# adc.net
KiCad netlist of a schematic drawn in Altium Designer
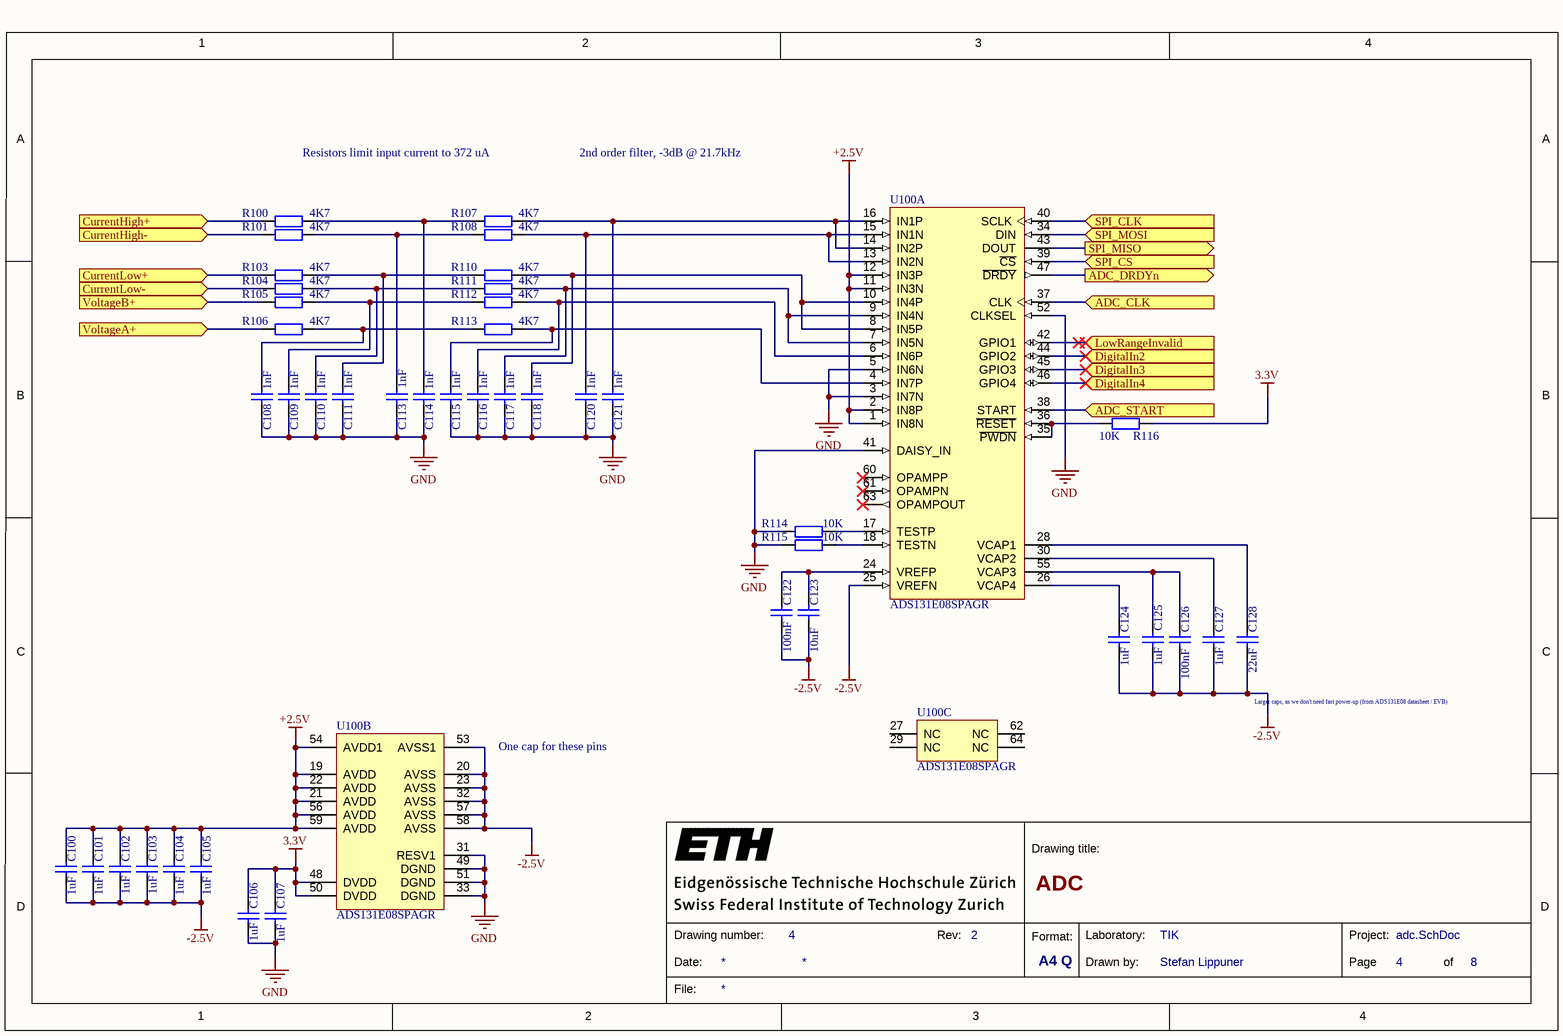
[diagram p0: adc.SchDoc]

(export (version "E")
  (design (tool "Eeschema 10.0.6"))
  (components
    (comp (ref "C100")
      (value "1uF")
      (footprint "CAPC0402(1005)60_L")
      (description "CAP 1uF 16V ±20% 0402 (1005 Metric) Thickness 0.6mm SMD")
      (fields (field (name "TOLERANCE") "Â±20%"))
      (libsource (lib "Altium Content Vault") (part "CMP-1034-02120"))
    )
    (comp (ref "C101")
      (value "1uF")
      (footprint "CAPC0402(1005)60_L")
      (description "CAP 1uF 16V ±20% 0402 (1005 Metric) Thickness 0.6mm SMD")
      (fields (field (name "TOLERANCE") "Â±20%"))
      (libsource (lib "Altium Content Vault") (part "CMP-1034-02120"))
    )
    (comp (ref "C102")
      (value "1uF")
      (footprint "CAPC0402(1005)60_L")
      (description "CAP 1uF 16V ±20% 0402 (1005 Metric) Thickness 0.6mm SMD")
      (fields (field (name "TOLERANCE") "Â±20%"))
      (libsource (lib "Altium Content Vault") (part "CMP-1034-02120"))
    )
    (comp (ref "C103")
      (value "1uF")
      (footprint "CAPC0402(1005)60_L")
      (description "CAP 1uF 16V ±20% 0402 (1005 Metric) Thickness 0.6mm SMD")
      (fields (field (name "TOLERANCE") "Â±20%"))
      (libsource (lib "Altium Content Vault") (part "CMP-1034-02120"))
    )
    (comp (ref "C104")
      (value "1uF")
      (footprint "CAPC0402(1005)60_L")
      (description "CAP 1uF 16V ±20% 0402 (1005 Metric) Thickness 0.6mm SMD")
      (fields (field (name "TOLERANCE") "Â±20%"))
      (libsource (lib "Altium Content Vault") (part "CMP-1034-02120"))
    )
    (comp (ref "C105")
      (value "1uF")
      (footprint "CAPC0402(1005)60_L")
      (description "CAP 1uF 16V ±20% 0402 (1005 Metric) Thickness 0.6mm SMD")
      (fields (field (name "TOLERANCE") "Â±20%"))
      (libsource (lib "Altium Content Vault") (part "CMP-1034-02120"))
    )
    (comp (ref "C106")
      (value "1uF")
      (footprint "CAPC0402(1005)60_L")
      (description "CAP 1uF 16V ±20% 0402 (1005 Metric) Thickness 0.6mm SMD")
      (fields (field (name "TOLERANCE") "Â±20%"))
      (libsource (lib "Altium Content Vault") (part "CMP-1034-02120"))
    )
    (comp (ref "C107")
      (value "1uF")
      (footprint "CAPC0402(1005)60_L")
      (description "CAP 1uF 16V ±20% 0402 (1005 Metric) Thickness 0.6mm SMD")
      (fields (field (name "TOLERANCE") "Â±20%"))
      (libsource (lib "Altium Content Vault") (part "CMP-1034-02120"))
    )
    (comp (ref "C108")
      (value "1nF")
      (footprint "CAPC0402(1005)60_L")
      (description "CAP 1nF 50V ±5% 0402 (1005 Metric) Thickness 0.6mm SMD")
      (fields (field (name "TOLERANCE") "Â±5%"))
      (libsource (lib "Altium Content Vault") (part "CAP"))
    )
    (comp (ref "C109")
      (value "1nF")
      (footprint "CAPC0402(1005)60_L")
      (description "CAP 1nF 50V ±5% 0402 (1005 Metric) Thickness 0.6mm SMD")
      (fields (field (name "TOLERANCE") "Â±5%"))
      (libsource (lib "Altium Content Vault") (part "CAP"))
    )
    (comp (ref "C110")
      (value "1nF")
      (footprint "CAPC0402(1005)60_L")
      (description "CAP 1nF 50V ±5% 0402 (1005 Metric) Thickness 0.6mm SMD")
      (fields (field (name "TOLERANCE") "Â±5%"))
      (libsource (lib "Altium Content Vault") (part "CAP"))
    )
    (comp (ref "C111")
      (value "1nF")
      (footprint "CAPC0402(1005)60_L")
      (description "CAP 1nF 50V ±5% 0402 (1005 Metric) Thickness 0.6mm SMD")
      (fields (field (name "TOLERANCE") "Â±5%"))
      (libsource (lib "Altium Content Vault") (part "CAP"))
    )
    (comp (ref "C113")
      (value "1nF")
      (footprint "CAPC0402(1005)60_L")
      (description "CAP 1nF 50V ±5% 0402 (1005 Metric) Thickness 0.6mm SMD")
      (fields (field (name "TOLERANCE") "Â±5%"))
      (libsource (lib "Altium Content Vault") (part "CAP"))
    )
    (comp (ref "C114")
      (value "1nF")
      (footprint "CAPC0402(1005)60_L")
      (description "CAP 1nF 50V ±5% 0402 (1005 Metric) Thickness 0.6mm SMD")
      (fields (field (name "TOLERANCE") "Â±5%"))
      (libsource (lib "Altium Content Vault") (part "CAP"))
    )
    (comp (ref "C115")
      (value "1nF")
      (footprint "CAPC0402(1005)60_L")
      (description "CAP 1nF 50V ±5% 0402 (1005 Metric) Thickness 0.6mm SMD")
      (fields (field (name "TOLERANCE") "Â±5%"))
      (libsource (lib "Altium Content Vault") (part "CAP"))
    )
    (comp (ref "C116")
      (value "1nF")
      (footprint "CAPC0402(1005)60_L")
      (description "CAP 1nF 50V ±5% 0402 (1005 Metric) Thickness 0.6mm SMD")
      (fields (field (name "TOLERANCE") "Â±5%"))
      (libsource (lib "Altium Content Vault") (part "CAP"))
    )
    (comp (ref "C117")
      (value "1nF")
      (footprint "CAPC0402(1005)60_L")
      (description "CAP 1nF 50V ±5% 0402 (1005 Metric) Thickness 0.6mm SMD")
      (fields (field (name "TOLERANCE") "Â±5%"))
      (libsource (lib "Altium Content Vault") (part "CAP"))
    )
    (comp (ref "C118")
      (value "1nF")
      (footprint "CAPC0402(1005)60_L")
      (description "CAP 1nF 50V ±5% 0402 (1005 Metric) Thickness 0.6mm SMD")
      (fields (field (name "TOLERANCE") "Â±5%"))
      (libsource (lib "Altium Content Vault") (part "CAP"))
    )
    (comp (ref "C120")
      (value "1nF")
      (footprint "CAPC0402(1005)60_L")
      (description "CAP 1nF 50V ±5% 0402 (1005 Metric) Thickness 0.6mm SMD")
      (fields (field (name "TOLERANCE") "Â±5%"))
      (libsource (lib "Altium Content Vault") (part "CAP"))
    )
    (comp (ref "C121")
      (value "1nF")
      (footprint "CAPC0402(1005)60_L")
      (description "CAP 1nF 50V ±5% 0402 (1005 Metric) Thickness 0.6mm SMD")
      (fields (field (name "TOLERANCE") "Â±5%"))
      (libsource (lib "Altium Content Vault") (part "CAP"))
    )
    (comp (ref "C122")
      (value "100nF")
      (footprint "CAPC0402(1005)60_L")
      (description "CAP 100nF 16V -20% to +80% 0402 (1005 Metric) Thickness 0.6mm SMD")
      (fields (field (name "TOLERANCE") "-20% to +80%"))
      (libsource (lib "Altium Content Vault") (part "CMP-1034-02071-1"))
    )
    (comp (ref "C123")
      (value "10uF")
      (footprint "CAPC0603(1608)100_L")
      (description "CAP 10uF 10V ±20% 0603 (1608 Metric) Thickness 1mm SMD")
      (fields (field (name "TOLERANCE") "Â±20%"))
      (libsource (lib "Altium Content Vault") (part "CMP-1035-02800-1"))
    )
    (comp (ref "C124")
      (value "1uF")
      (footprint "CAPC0402(1005)60_L")
      (description "CAP 1uF 16V ±20% 0402 (1005 Metric) Thickness 0.6mm SMD")
      (fields (field (name "TOLERANCE") "Â±20%"))
      (libsource (lib "Altium Content Vault") (part "CMP-1034-02120"))
    )
    (comp (ref "C125")
      (value "1uF")
      (footprint "CAPC0402(1005)60_L")
      (description "CAP 1uF 16V ±20% 0402 (1005 Metric) Thickness 0.6mm SMD")
      (fields (field (name "TOLERANCE") "Â±20%"))
      (libsource (lib "Altium Content Vault") (part "CMP-1034-02120"))
    )
    (comp (ref "C126")
      (value "100nF")
      (footprint "CAPC0402(1005)60_L")
      (description "CAP 100nF 16V -20% to +80% 0402 (1005 Metric) Thickness 0.6mm SMD")
      (fields (field (name "TOLERANCE") "-20% to +80%"))
      (libsource (lib "Altium Content Vault") (part "CMP-1034-02071-1"))
    )
    (comp (ref "C127")
      (value "1uF")
      (footprint "CAPC0402(1005)60_L")
      (description "CAP 1uF 16V ±20% 0402 (1005 Metric) Thickness 0.6mm SMD")
      (fields (field (name "TOLERANCE") "Â±20%"))
      (libsource (lib "Altium Content Vault") (part "CMP-1034-02120"))
    )
    (comp (ref "C128")
      (value "22uF")
      (footprint "CAPC0805(2012)145_L")
      (description "CAP 22uF 6.3V ±10% 0805 (2012 Metric) Thickness 1.45mm SMD")
      (fields (field (name "TOLERANCE") "Â±10%"))
      (libsource (lib "Altium Content Vault") (part "CAP"))
    )
    (comp (ref "R100")
      (value "4K7")
      (footprint "RESC0402(1005)_L")
      (description "4K7 0.063W 1% 0402 (1005 Metric)  SMD")
      (fields (field (name "POWER") "0.063 W") (field (name "TOLERANCE") "1 %"))
      (libsource (lib "Altium Content Vault") (part "RES"))
    )
    (comp (ref "R101")
      (value "4K7")
      (footprint "RESC0402(1005)_L")
      (description "4K7 0.063W 1% 0402 (1005 Metric)  SMD")
      (fields (field (name "POWER") "0.063 W") (field (name "TOLERANCE") "1 %"))
      (libsource (lib "Altium Content Vault") (part "RES"))
    )
    (comp (ref "R103")
      (value "4K7")
      (footprint "RESC0402(1005)_L")
      (description "4K7 0.063W 1% 0402 (1005 Metric)  SMD")
      (fields (field (name "POWER") "0.063 W") (field (name "TOLERANCE") "1 %"))
      (libsource (lib "Altium Content Vault") (part "RES"))
    )
    (comp (ref "R104")
      (value "4K7")
      (footprint "RESC0402(1005)_L")
      (description "4K7 0.063W 1% 0402 (1005 Metric)  SMD")
      (fields (field (name "POWER") "0.063 W") (field (name "TOLERANCE") "1 %"))
      (libsource (lib "Altium Content Vault") (part "RES"))
    )
    (comp (ref "R105")
      (value "4K7")
      (footprint "RESC0402(1005)_L")
      (description "4K7 0.063W 1% 0402 (1005 Metric)  SMD")
      (fields (field (name "POWER") "0.063 W") (field (name "TOLERANCE") "1 %"))
      (libsource (lib "Altium Content Vault") (part "RES"))
    )
    (comp (ref "R106")
      (value "4K7")
      (footprint "RESC0402(1005)_L")
      (description "4K7 0.063W 1% 0402 (1005 Metric)  SMD")
      (fields (field (name "POWER") "0.063 W") (field (name "TOLERANCE") "1 %"))
      (libsource (lib "Altium Content Vault") (part "RES"))
    )
    (comp (ref "R107")
      (value "4K7")
      (footprint "RESC0402(1005)_L")
      (description "4K7 0.063W 1% 0402 (1005 Metric)  SMD")
      (fields (field (name "POWER") "0.063 W") (field (name "TOLERANCE") "1 %"))
      (libsource (lib "Altium Content Vault") (part "RES"))
    )
    (comp (ref "R108")
      (value "4K7")
      (footprint "RESC0402(1005)_L")
      (description "4K7 0.063W 1% 0402 (1005 Metric)  SMD")
      (fields (field (name "POWER") "0.063 W") (field (name "TOLERANCE") "1 %"))
      (libsource (lib "Altium Content Vault") (part "RES"))
    )
    (comp (ref "R110")
      (value "4K7")
      (footprint "RESC0402(1005)_L")
      (description "4K7 0.063W 1% 0402 (1005 Metric)  SMD")
      (fields (field (name "POWER") "0.063 W") (field (name "TOLERANCE") "1 %"))
      (libsource (lib "Altium Content Vault") (part "RES"))
    )
    (comp (ref "R111")
      (value "4K7")
      (footprint "RESC0402(1005)_L")
      (description "4K7 0.063W 1% 0402 (1005 Metric)  SMD")
      (fields (field (name "POWER") "0.063 W") (field (name "TOLERANCE") "1 %"))
      (libsource (lib "Altium Content Vault") (part "RES"))
    )
    (comp (ref "R112")
      (value "4K7")
      (footprint "RESC0402(1005)_L")
      (description "4K7 0.063W 1% 0402 (1005 Metric)  SMD")
      (fields (field (name "POWER") "0.063 W") (field (name "TOLERANCE") "1 %"))
      (libsource (lib "Altium Content Vault") (part "RES"))
    )
    (comp (ref "R113")
      (value "4K7")
      (footprint "RESC0402(1005)_L")
      (description "4K7 0.063W 1% 0402 (1005 Metric)  SMD")
      (fields (field (name "POWER") "0.063 W") (field (name "TOLERANCE") "1 %"))
      (libsource (lib "Altium Content Vault") (part "RES"))
    )
    (comp (ref "R114")
      (value "10K")
      (footprint "RESC0402(1005)_L")
      (description "10K 0.063W 1% 0402 (1005 Metric)  SMD")
      (fields (field (name "TOLERANCE") "1 %") (field (name "POWER") "0.063 W"))
      (libsource (lib "Altium Content Vault") (part "CMP-1011-00623-1"))
    )
    (comp (ref "R115")
      (value "10K")
      (footprint "RESC0402(1005)_L")
      (description "10K 0.063W 1% 0402 (1005 Metric)  SMD")
      (fields (field (name "TOLERANCE") "1 %") (field (name "POWER") "0.063 W"))
      (libsource (lib "Altium Content Vault") (part "CMP-1011-00623-1"))
    )
    (comp (ref "R116")
      (value "10K")
      (footprint "RESC0402(1005)_L")
      (description "10K 0.063W 1% 0402 (1005 Metric)  SMD")
      (fields (field (name "TOLERANCE") "1 %") (field (name "POWER") "0.063 W"))
      (libsource (lib "Altium Content Vault") (part "RES"))
    )
    (comp (ref "U100")
      (value "ADS131E08SPAGR")
      (footprint "QFP50P1000X1000X120_HS-64L")
      (description "Analog to Digital Converters - ADC 8-Channel, 24-Bit, AFE")
      (fields (field (name "MANUFACTURER") "Texas Instruments"))
      (libsource (lib "ETHZ Vault") (part "ADS131E08S"))
    )
  )
  (nets
    (net (code "1") (name "+2.5V") (class "Default")
      (node (ref "C100") (pin "2") (pinfunction "2_2") (pintype "passive"))
      (node (ref "C101") (pin "2") (pinfunction "2_2") (pintype "passive"))
      (node (ref "C102") (pin "2") (pinfunction "2_2") (pintype "passive"))
      (node (ref "C103") (pin "2") (pinfunction "2_2") (pintype "passive"))
      (node (ref "C104") (pin "2") (pinfunction "2_2") (pintype "passive"))
      (node (ref "C105") (pin "2") (pinfunction "2_2") (pintype "passive"))
      (node (ref "U100") (pin "1") (pinfunction "IN8N_1") (pintype "input"))
      (node (ref "U100") (pin "11") (pinfunction "IN3N_11") (pintype "input"))
      (node (ref "U100") (pin "12") (pinfunction "IN3P_12") (pintype "input"))
      (node (ref "U100") (pin "19") (pinfunction "AVDD_19") (pintype "power_in"))
      (node (ref "U100") (pin "2") (pinfunction "IN8P_2") (pintype "input"))
      (node (ref "U100") (pin "21") (pinfunction "AVDD_21") (pintype "power_in"))
      (node (ref "U100") (pin "22") (pinfunction "AVDD_22") (pintype "power_in"))
      (node (ref "U100") (pin "54") (pinfunction "AVDD1_54") (pintype "power_in"))
      (node (ref "U100") (pin "56") (pinfunction "AVDD_56") (pintype "power_in"))
      (node (ref "U100") (pin "59") (pinfunction "AVDD_59") (pintype "power_in"))
    )
    (net (code "2") (name "-2.5V") (class "Default")
      (node (ref "C100") (pin "1") (pinfunction "1_1") (pintype "passive"))
      (node (ref "C101") (pin "1") (pinfunction "1_1") (pintype "passive"))
      (node (ref "C102") (pin "1") (pinfunction "1_1") (pintype "passive"))
      (node (ref "C103") (pin "1") (pinfunction "1_1") (pintype "passive"))
      (node (ref "C104") (pin "1") (pinfunction "1_1") (pintype "passive"))
      (node (ref "C105") (pin "1") (pinfunction "1_1") (pintype "passive"))
      (node (ref "C122") (pin "1") (pinfunction "1_1") (pintype "passive"))
      (node (ref "C123") (pin "1") (pinfunction "1_1") (pintype "passive"))
      (node (ref "C124") (pin "1") (pinfunction "1_1") (pintype "passive"))
      (node (ref "C125") (pin "1") (pinfunction "1_1") (pintype "passive"))
      (node (ref "C126") (pin "1") (pinfunction "1_1") (pintype "passive"))
      (node (ref "C127") (pin "1") (pinfunction "1_1") (pintype "passive"))
      (node (ref "C128") (pin "1") (pinfunction "1_1") (pintype "passive"))
      (node (ref "U100") (pin "20") (pinfunction "AVSS_20") (pintype "power_in"))
      (node (ref "U100") (pin "23") (pinfunction "AVSS_23") (pintype "power_in"))
      (node (ref "U100") (pin "25") (pinfunction "VREFN_25") (pintype "input"))
      (node (ref "U100") (pin "32") (pinfunction "AVSS_32") (pintype "power_in"))
      (node (ref "U100") (pin "53") (pinfunction "AVSS1_53") (pintype "power_in"))
      (node (ref "U100") (pin "57") (pinfunction "AVSS_57") (pintype "power_in"))
      (node (ref "U100") (pin "58") (pinfunction "AVSS_58") (pintype "power_in"))
    )
    (net (code "3") (name "/ADC_CLK") (class "Default")
      (node (ref "U100") (pin "37") (pinfunction "CLK_37") (pintype "input"))
    )
    (net (code "4") (name "/ADC_DRDYn") (class "Default")
      (node (ref "U100") (pin "47") (pinfunction "~{DRDY}_47") (pintype "output"))
    )
    (net (code "5") (name "/ADC_START") (class "Default")
      (node (ref "U100") (pin "38") (pinfunction "START_38") (pintype "input"))
    )
    (net (code "6") (name "/CurrentHigh+") (class "Default")
      (node (ref "R100") (pin "2") (pinfunction "2_2") (pintype "passive"))
    )
    (net (code "7") (name "/CurrentHigh-") (class "Default")
      (node (ref "R101") (pin "2") (pinfunction "2_2") (pintype "passive"))
    )
    (net (code "8") (name "/CurrentLow+") (class "Default")
      (node (ref "R103") (pin "2") (pinfunction "2_2") (pintype "passive"))
    )
    (net (code "9") (name "/CurrentLow-") (class "Default")
      (node (ref "R104") (pin "2") (pinfunction "2_2") (pintype "passive"))
    )
    (net (code "10") (name "/DigitalIn2") (class "Default")
      (node (ref "U100") (pin "44") (pinfunction "GPIO2_44") (pintype "bidirectional+no_connect"))
    )
    (net (code "11") (name "/DigitalIn3") (class "Default")
      (node (ref "U100") (pin "45") (pinfunction "GPIO3_45") (pintype "bidirectional+no_connect"))
    )
    (net (code "12") (name "/DigitalIn4") (class "Default")
      (node (ref "U100") (pin "46") (pinfunction "GPIO4_46") (pintype "bidirectional+no_connect"))
    )
    (net (code "13") (name "/LowRangeInvalid") (class "Default")
      (node (ref "U100") (pin "42") (pinfunction "GPIO1_42") (pintype "bidirectional+no_connect"))
    )
    (net (code "14") (name "/SPI_CLK") (class "Default")
      (node (ref "U100") (pin "40") (pinfunction "SCLK_40") (pintype "input"))
    )
    (net (code "15") (name "/SPI_CS") (class "Default")
      (node (ref "U100") (pin "39") (pinfunction "~{CS}_39") (pintype "input"))
    )
    (net (code "16") (name "/SPI_MISO") (class "Default")
      (node (ref "U100") (pin "43") (pinfunction "DOUT_43") (pintype "tri_state"))
    )
    (net (code "17") (name "/SPI_MOSI") (class "Default")
      (node (ref "U100") (pin "34") (pinfunction "DIN_34") (pintype "input"))
    )
    (net (code "18") (name "/VoltageA+") (class "Default")
      (node (ref "R106") (pin "2") (pinfunction "2_2") (pintype "passive"))
    )
    (net (code "19") (name "/VoltageB+") (class "Default")
      (node (ref "R105") (pin "2") (pinfunction "2_2") (pintype "passive"))
    )
    (net (code "20") (name "3.3V") (class "Default")
      (node (ref "C106") (pin "2") (pinfunction "2_2") (pintype "passive"))
      (node (ref "C107") (pin "2") (pinfunction "2_2") (pintype "passive"))
      (node (ref "R116") (pin "1") (pinfunction "1_1") (pintype "passive"))
      (node (ref "U100") (pin "48") (pinfunction "DVDD_48") (pintype "power_in"))
      (node (ref "U100") (pin "50") (pinfunction "DVDD_50") (pintype "power_in"))
    )
    (net (code "21") (name "GND") (class "Default")
      (node (ref "C106") (pin "1") (pinfunction "1_1") (pintype "passive"))
      (node (ref "C107") (pin "1") (pinfunction "1_1") (pintype "passive"))
      (node (ref "C108") (pin "1") (pinfunction "1_1") (pintype "passive"))
      (node (ref "C109") (pin "1") (pinfunction "1_1") (pintype "passive"))
      (node (ref "C110") (pin "1") (pinfunction "1_1") (pintype "passive"))
      (node (ref "C111") (pin "1") (pinfunction "1_1") (pintype "passive"))
      (node (ref "C113") (pin "1") (pinfunction "1_1") (pintype "passive"))
      (node (ref "C114") (pin "1") (pinfunction "1_1") (pintype "passive"))
      (node (ref "C115") (pin "1") (pinfunction "1_1") (pintype "passive"))
      (node (ref "C116") (pin "1") (pinfunction "1_1") (pintype "passive"))
      (node (ref "C117") (pin "1") (pinfunction "1_1") (pintype "passive"))
      (node (ref "C118") (pin "1") (pinfunction "1_1") (pintype "passive"))
      (node (ref "C120") (pin "1") (pinfunction "1_1") (pintype "passive"))
      (node (ref "C121") (pin "1") (pinfunction "1_1") (pintype "passive"))
      (node (ref "R114") (pin "1") (pinfunction "1_1") (pintype "passive"))
      (node (ref "R115") (pin "1") (pinfunction "1_1") (pintype "passive"))
      (node (ref "U100") (pin "3") (pinfunction "IN7N_3") (pintype "input"))
      (node (ref "U100") (pin "31") (pinfunction "RESV1_31") (pintype "power_in"))
      (node (ref "U100") (pin "33") (pinfunction "DGND_33") (pintype "power_in"))
      (node (ref "U100") (pin "41") (pinfunction "DAISY_IN_41") (pintype "input"))
      (node (ref "U100") (pin "49") (pinfunction "DGND_49") (pintype "power_in"))
      (node (ref "U100") (pin "5") (pinfunction "IN6N_5") (pintype "input"))
      (node (ref "U100") (pin "51") (pinfunction "DGND_51") (pintype "power_in"))
      (node (ref "U100") (pin "52") (pinfunction "CLKSEL_52") (pintype "input"))
    )
    (net (code "22") (name "Net-(C108-Pad2)") (class "Default")
      (node (ref "C108") (pin "2") (pinfunction "2_2") (pintype "passive"))
      (node (ref "R106") (pin "1") (pinfunction "1_1") (pintype "passive"))
      (node (ref "R113") (pin "2") (pinfunction "2_2") (pintype "passive"))
    )
    (net (code "23") (name "Net-(C109-Pad2)") (class "Default")
      (node (ref "C109") (pin "2") (pinfunction "2_2") (pintype "passive"))
      (node (ref "R105") (pin "1") (pinfunction "1_1") (pintype "passive"))
      (node (ref "R112") (pin "2") (pinfunction "2_2") (pintype "passive"))
    )
    (net (code "24") (name "Net-(C110-Pad2)") (class "Default")
      (node (ref "C110") (pin "2") (pinfunction "2_2") (pintype "passive"))
      (node (ref "R104") (pin "1") (pinfunction "1_1") (pintype "passive"))
      (node (ref "R111") (pin "2") (pinfunction "2_2") (pintype "passive"))
    )
    (net (code "25") (name "Net-(C111-Pad2)") (class "Default")
      (node (ref "C111") (pin "2") (pinfunction "2_2") (pintype "passive"))
      (node (ref "R103") (pin "1") (pinfunction "1_1") (pintype "passive"))
      (node (ref "R110") (pin "2") (pinfunction "2_2") (pintype "passive"))
    )
    (net (code "26") (name "Net-(C113-Pad2)") (class "Default")
      (node (ref "C113") (pin "2") (pinfunction "2_2") (pintype "passive"))
      (node (ref "R101") (pin "1") (pinfunction "1_1") (pintype "passive"))
      (node (ref "R108") (pin "2") (pinfunction "2_2") (pintype "passive"))
    )
    (net (code "27") (name "Net-(C114-Pad2)") (class "Default")
      (node (ref "C114") (pin "2") (pinfunction "2_2") (pintype "passive"))
      (node (ref "R100") (pin "1") (pinfunction "1_1") (pintype "passive"))
      (node (ref "R107") (pin "2") (pinfunction "2_2") (pintype "passive"))
    )
    (net (code "28") (name "Net-(U100A-IN1N)") (class "Default")
      (node (ref "C120") (pin "2") (pinfunction "2_2") (pintype "passive"))
      (node (ref "R108") (pin "1") (pinfunction "1_1") (pintype "passive"))
      (node (ref "U100") (pin "13") (pinfunction "IN2N_13") (pintype "input"))
      (node (ref "U100") (pin "15") (pinfunction "IN1N_15") (pintype "input"))
    )
    (net (code "29") (name "Net-(U100A-IN1P)") (class "Default")
      (node (ref "C121") (pin "2") (pinfunction "2_2") (pintype "passive"))
      (node (ref "R107") (pin "1") (pinfunction "1_1") (pintype "passive"))
      (node (ref "U100") (pin "14") (pinfunction "IN2P_14") (pintype "input"))
      (node (ref "U100") (pin "16") (pinfunction "IN1P_16") (pintype "input"))
    )
    (net (code "30") (name "Net-(U100A-IN4N)") (class "Default")
      (node (ref "C117") (pin "2") (pinfunction "2_2") (pintype "passive"))
      (node (ref "R111") (pin "1") (pinfunction "1_1") (pintype "passive"))
      (node (ref "U100") (pin "7") (pinfunction "IN5N_7") (pintype "input"))
      (node (ref "U100") (pin "9") (pinfunction "IN4N_9") (pintype "input"))
    )
    (net (code "31") (name "Net-(U100A-IN4P)") (class "Default")
      (node (ref "C118") (pin "2") (pinfunction "2_2") (pintype "passive"))
      (node (ref "R110") (pin "1") (pinfunction "1_1") (pintype "passive"))
      (node (ref "U100") (pin "10") (pinfunction "IN4P_10") (pintype "input"))
      (node (ref "U100") (pin "8") (pinfunction "IN5P_8") (pintype "input"))
    )
    (net (code "32") (name "Net-(U100A-IN6P)") (class "Default")
      (node (ref "C116") (pin "2") (pinfunction "2_2") (pintype "passive"))
      (node (ref "R112") (pin "1") (pinfunction "1_1") (pintype "passive"))
      (node (ref "U100") (pin "6") (pinfunction "IN6P_6") (pintype "input"))
    )
    (net (code "33") (name "Net-(U100A-IN7P)") (class "Default")
      (node (ref "C115") (pin "2") (pinfunction "2_2") (pintype "passive"))
      (node (ref "R113") (pin "1") (pinfunction "1_1") (pintype "passive"))
      (node (ref "U100") (pin "4") (pinfunction "IN7P_4") (pintype "input"))
    )
    (net (code "34") (name "Net-(U100A-TESTN)") (class "Default")
      (node (ref "R115") (pin "2") (pinfunction "2_2") (pintype "passive"))
      (node (ref "U100") (pin "18") (pinfunction "TESTN_18") (pintype "input"))
    )
    (net (code "35") (name "Net-(U100A-TESTP)") (class "Default")
      (node (ref "R114") (pin "2") (pinfunction "2_2") (pintype "passive"))
      (node (ref "U100") (pin "17") (pinfunction "TESTP_17") (pintype "input"))
    )
    (net (code "36") (name "Net-(U100A-VCAP1)") (class "Default")
      (node (ref "C128") (pin "2") (pinfunction "2_2") (pintype "passive"))
      (node (ref "U100") (pin "28") (pinfunction "VCAP1_28") (pintype "passive"))
    )
    (net (code "37") (name "Net-(U100A-VCAP2)") (class "Default")
      (node (ref "C127") (pin "2") (pinfunction "2_2") (pintype "passive"))
      (node (ref "U100") (pin "30") (pinfunction "VCAP2_30") (pintype "passive"))
    )
    (net (code "38") (name "Net-(U100A-VCAP3)") (class "Default")
      (node (ref "C125") (pin "2") (pinfunction "2_2") (pintype "passive"))
      (node (ref "C126") (pin "2") (pinfunction "2_2") (pintype "passive"))
      (node (ref "U100") (pin "55") (pinfunction "VCAP3_55") (pintype "passive"))
    )
    (net (code "39") (name "Net-(U100A-VCAP4)") (class "Default")
      (node (ref "C124") (pin "2") (pinfunction "2_2") (pintype "passive"))
      (node (ref "U100") (pin "26") (pinfunction "VCAP4_26") (pintype "passive"))
    )
    (net (code "40") (name "Net-(U100A-VREFP)") (class "Default")
      (node (ref "C122") (pin "2") (pinfunction "2_2") (pintype "passive"))
      (node (ref "C123") (pin "2") (pinfunction "2_2") (pintype "passive"))
      (node (ref "U100") (pin "24") (pinfunction "VREFP_24") (pintype "input"))
    )
    (net (code "41") (name "Net-(U100A-~{PWDN})") (class "Default")
      (node (ref "R116") (pin "2") (pinfunction "2_2") (pintype "passive"))
      (node (ref "U100") (pin "35") (pinfunction "~{PWDN}_35") (pintype "input"))
      (node (ref "U100") (pin "36") (pinfunction "~{RESET}_36") (pintype "input"))
    )
    (net (code "42") (name "unconnected-(U100A-OPAMPN-Pad61)") (class "Default")
      (node (ref "U100") (pin "61") (pinfunction "OPAMPN_61") (pintype "input+no_connect"))
    )
    (net (code "43") (name "unconnected-(U100A-OPAMPOUT-Pad63)") (class "Default")
      (node (ref "U100") (pin "63") (pinfunction "OPAMPOUT_63") (pintype "output+no_connect"))
    )
    (net (code "44") (name "unconnected-(U100A-OPAMPP-Pad60)") (class "Default")
      (node (ref "U100") (pin "60") (pinfunction "OPAMPP_60") (pintype "input+no_connect"))
    )
    (net (code "45") (name "unconnected-(U100C-NC-Pad27)") (class "Default")
      (node (ref "U100") (pin "27") (pinfunction "NC_27") (pintype "passive"))
    )
    (net (code "46") (name "unconnected-(U100C-NC-Pad29)") (class "Default")
      (node (ref "U100") (pin "29") (pinfunction "NC_29") (pintype "passive"))
    )
    (net (code "47") (name "unconnected-(U100C-NC-Pad62)") (class "Default")
      (node (ref "U100") (pin "62") (pinfunction "NC_62") (pintype "passive"))
    )
    (net (code "48") (name "unconnected-(U100C-NC-Pad64)") (class "Default")
      (node (ref "U100") (pin "64") (pinfunction "NC_64") (pintype "passive"))
    )
  )
)
